# Codec.net
KiCad netlist of a schematic drawn in Altium Designer
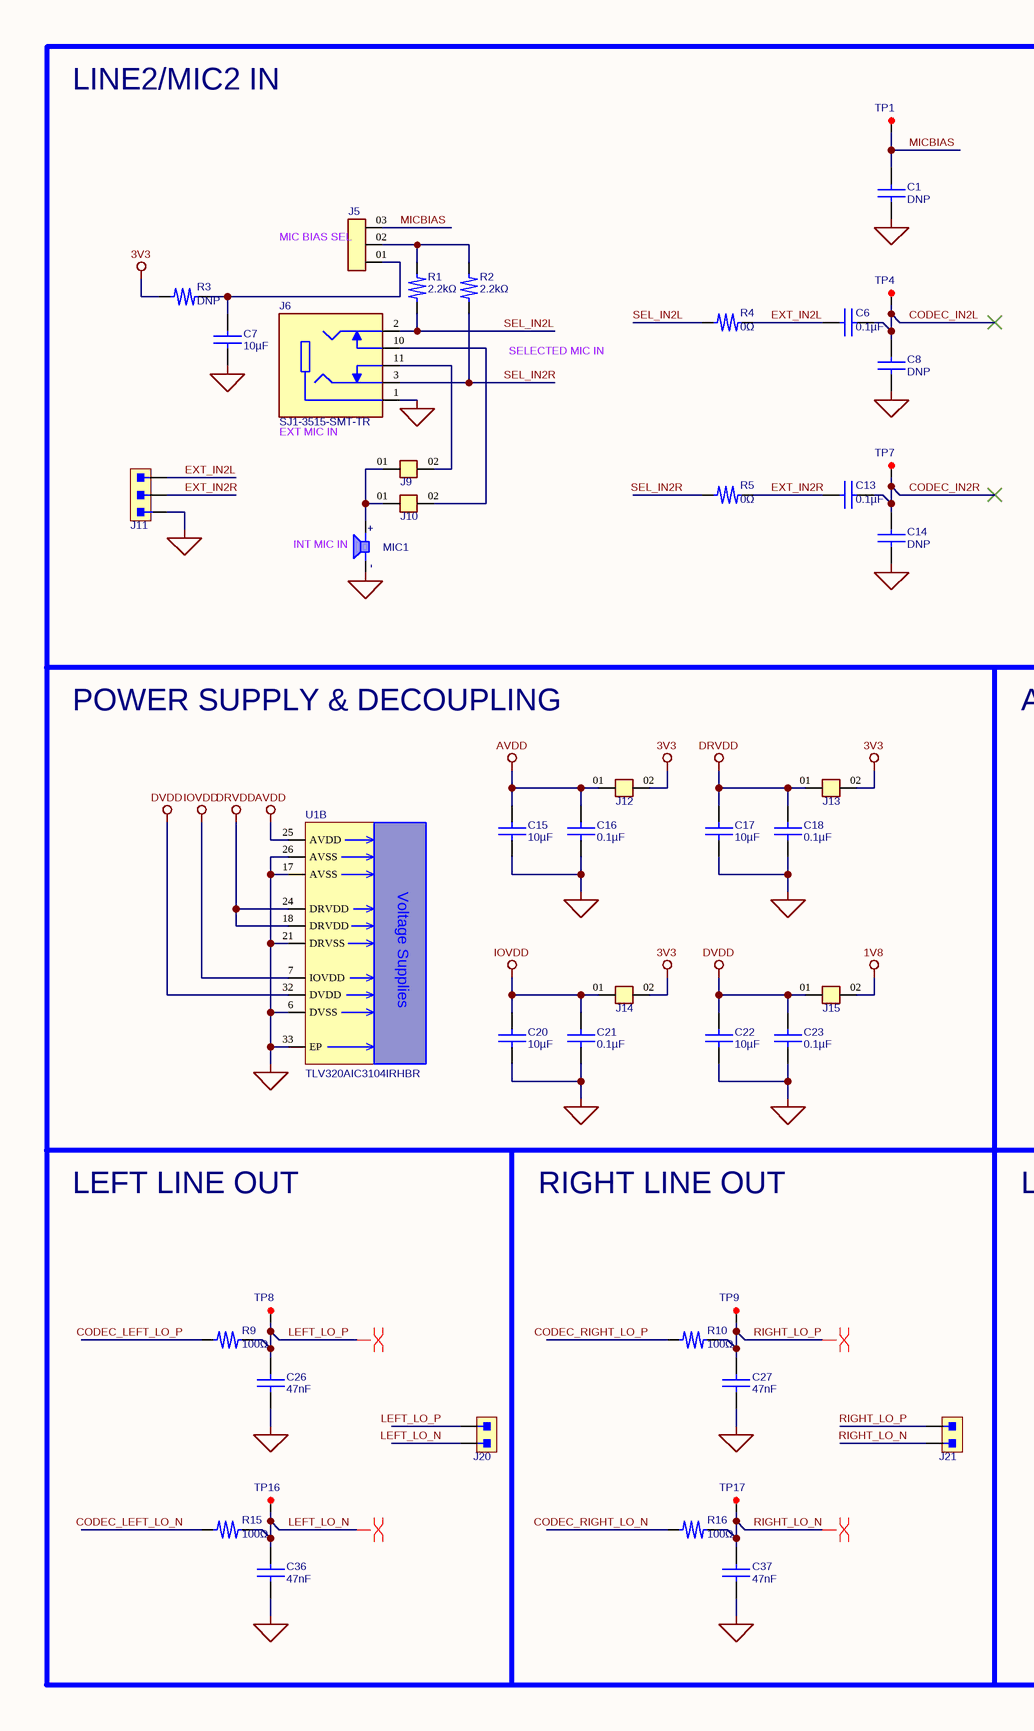
[diagram p0: Codec.SchDoc, left]
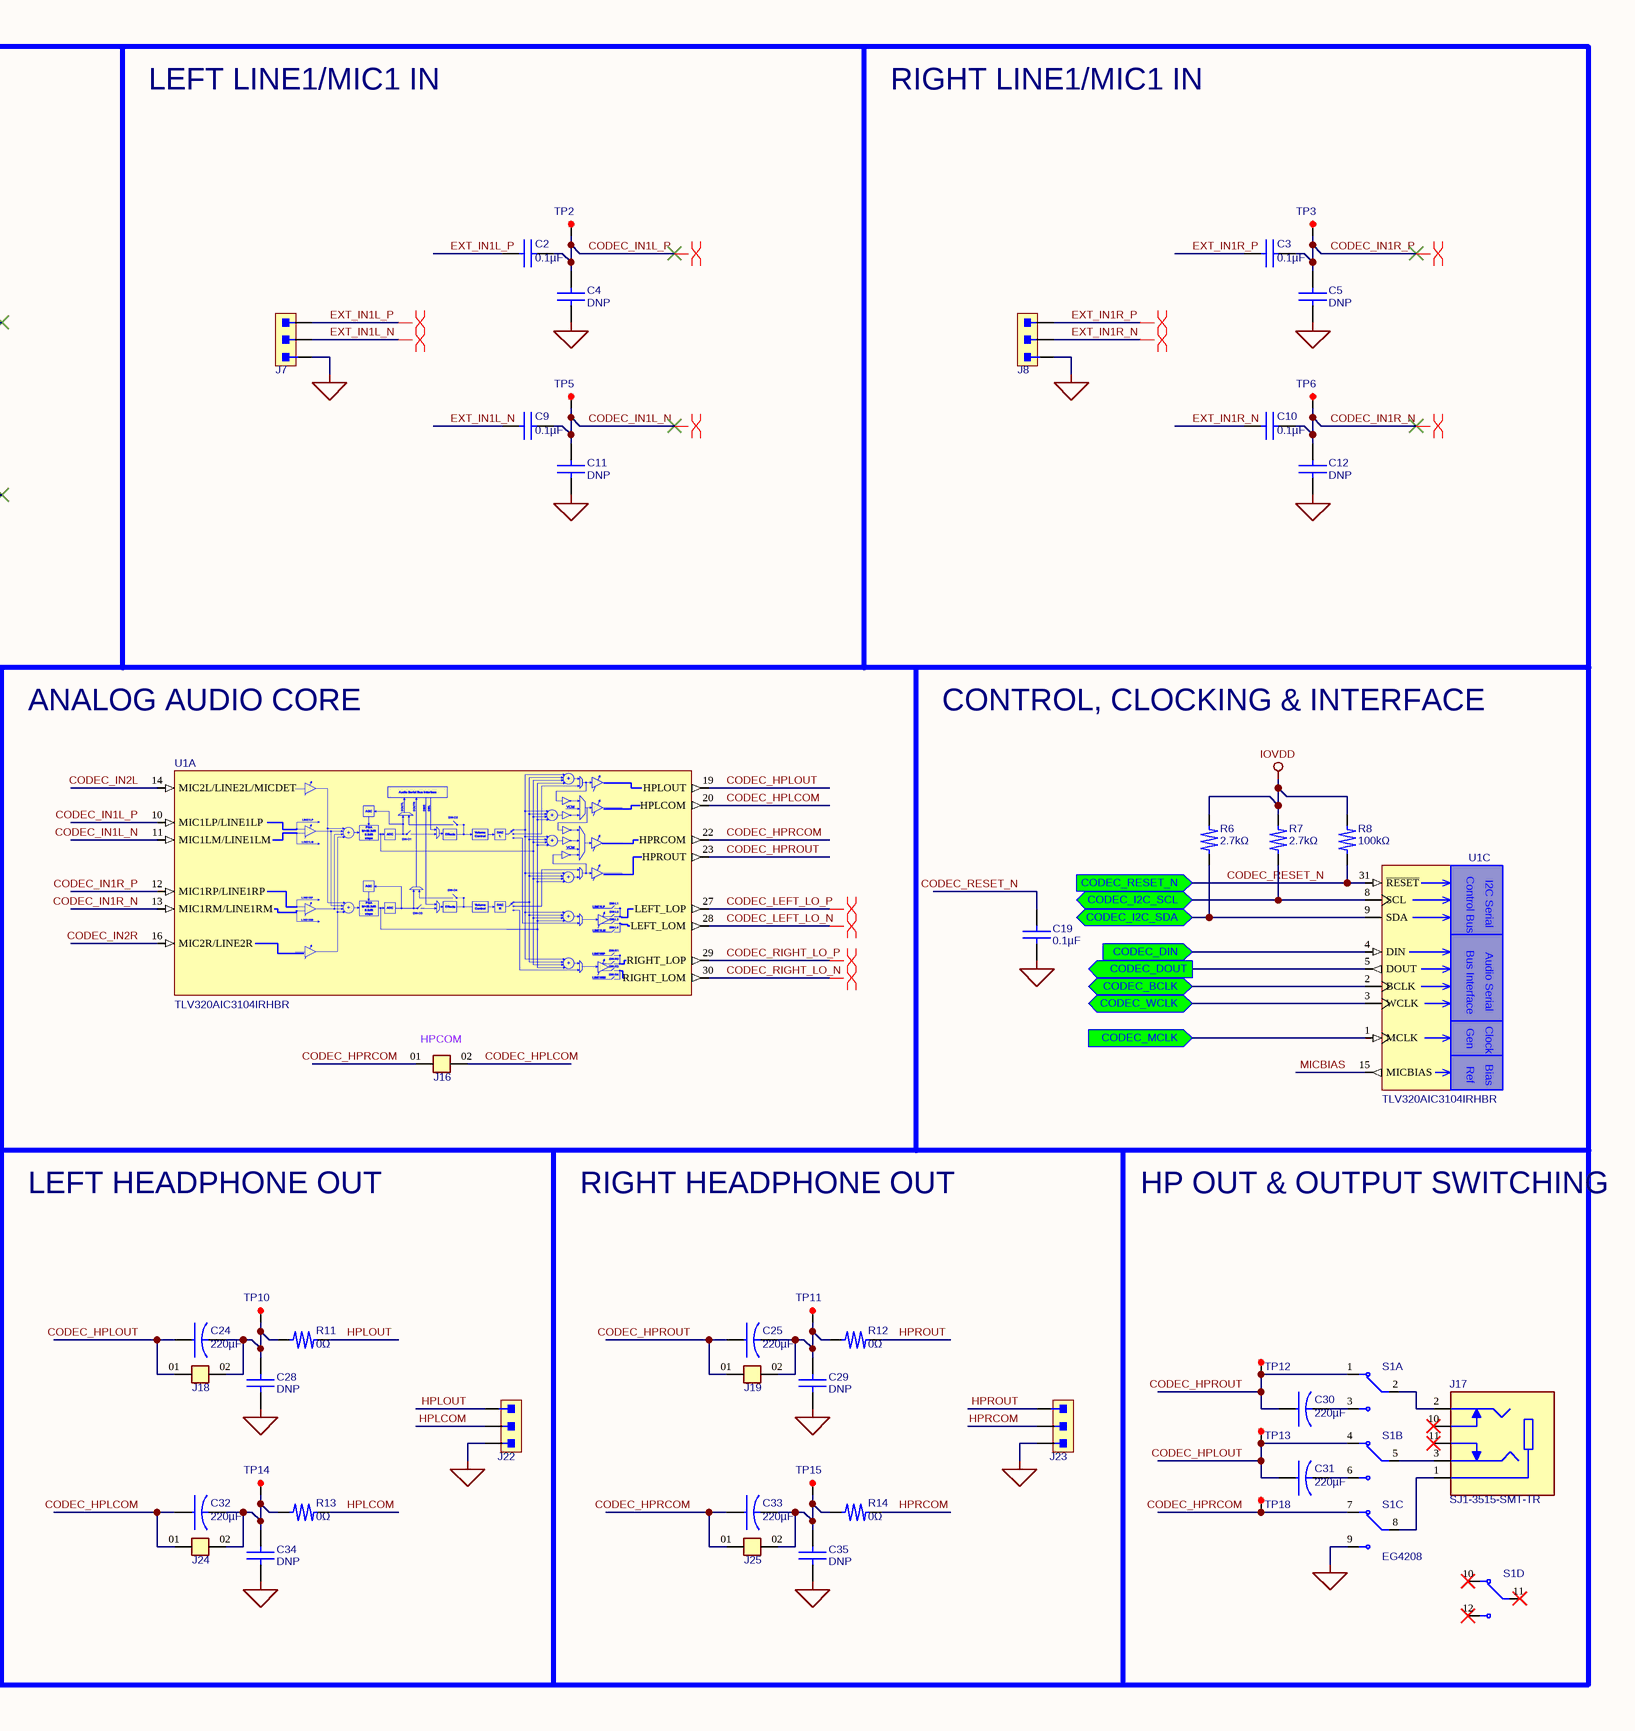
[diagram p1: Codec.SchDoc, right]

(export (version "E")
  (design (tool "Eeschema 10.0.6"))
  (components
    (comp (ref "C1")
      (value "DNP")
      (footprint "CAPC3216")
      (description "Do Not Populate 1206 (3216 Metric)")
      (fields (field (name "Comment") "DNP_1206"))
      (libsource (lib "Capacitors") (part "DNP_1206"))
    )
    (comp (ref "C2")
      (value "0.1µF")
      (footprint "CAPC3216")
      (description "Multilayer Ceramic Capacitor, C Series, 0.1 - F, - 10%, X7R, 100 V, 1206 [3216 Metric]")
      (fields
        (field (name "MANUFACTURER") "TDK")
        (field (name "MANUFACTURER PART NUMBER") "C3216X7R2A104K160AA")
      )
      (libsource (lib "Capacitors") (part "C3216X7R2A104K160AA"))
    )
    (comp (ref "C3")
      (value "0.1µF")
      (footprint "CAPC3216")
      (description "Multilayer Ceramic Capacitor, C Series, 0.1 - F, - 10%, X7R, 100 V, 1206 [3216 Metric]")
      (fields
        (field (name "MANUFACTURER") "TDK")
        (field (name "MANUFACTURER PART NUMBER") "C3216X7R2A104K160AA")
      )
      (libsource (lib "Capacitors") (part "C3216X7R2A104K160AA"))
    )
    (comp (ref "C4")
      (value "DNP")
      (footprint "CAPC3216")
      (description "Do Not Populate 1206 (3216 Metric)")
      (fields (field (name "Comment") "DNP_1206"))
      (libsource (lib "Capacitors") (part "DNP_1206"))
    )
    (comp (ref "C5")
      (value "DNP")
      (footprint "CAPC3216")
      (description "Do Not Populate 1206 (3216 Metric)")
      (fields (field (name "Comment") "DNP_1206"))
      (libsource (lib "Capacitors") (part "DNP_1206"))
    )
    (comp (ref "C6")
      (value "0.1µF")
      (footprint "CAPC3216")
      (description "Multilayer Ceramic Capacitor, C Series, 0.1 - F, - 10%, X7R, 100 V, 1206 [3216 Metric]")
      (fields
        (field (name "MANUFACTURER") "TDK")
        (field (name "MANUFACTURER PART NUMBER") "C3216X7R2A104K160AA")
      )
      (libsource (lib "Capacitors") (part "C3216X7R2A104K160AA"))
    )
    (comp (ref "C7")
      (value "10µF")
      (footprint "CAPC3225")
      (fields
        (field (name "MANUFACTURER") "TDK")
        (field (name "MANUFACTURER PART NUMBER") "C3225X7R1H106K250AC")
      )
      (libsource (lib "Capacitors") (part "C3225X7R1H106K250AC"))
    )
    (comp (ref "C8")
      (value "DNP")
      (footprint "CAPC3216")
      (description "Do Not Populate 1206 (3216 Metric)")
      (fields (field (name "Comment") "DNP_1206"))
      (libsource (lib "Capacitors") (part "DNP_1206"))
    )
    (comp (ref "C9")
      (value "0.1µF")
      (footprint "CAPC3216")
      (description "Multilayer Ceramic Capacitor, C Series, 0.1 - F, - 10%, X7R, 100 V, 1206 [3216 Metric]")
      (fields
        (field (name "MANUFACTURER") "TDK")
        (field (name "MANUFACTURER PART NUMBER") "C3216X7R2A104K160AA")
      )
      (libsource (lib "Capacitors") (part "C3216X7R2A104K160AA"))
    )
    (comp (ref "C10")
      (value "0.1µF")
      (footprint "CAPC3216")
      (description "Multilayer Ceramic Capacitor, C Series, 0.1 - F, - 10%, X7R, 100 V, 1206 [3216 Metric]")
      (fields
        (field (name "MANUFACTURER") "TDK")
        (field (name "MANUFACTURER PART NUMBER") "C3216X7R2A104K160AA")
      )
      (libsource (lib "Capacitors") (part "C3216X7R2A104K160AA"))
    )
    (comp (ref "C11")
      (value "DNP")
      (footprint "CAPC3216")
      (description "Do Not Populate 1206 (3216 Metric)")
      (fields (field (name "Comment") "DNP_1206"))
      (libsource (lib "Capacitors") (part "DNP_1206"))
    )
    (comp (ref "C12")
      (value "DNP")
      (footprint "CAPC3216")
      (description "Do Not Populate 1206 (3216 Metric)")
      (fields (field (name "Comment") "DNP_1206"))
      (libsource (lib "Capacitors") (part "DNP_1206"))
    )
    (comp (ref "C13")
      (value "0.1µF")
      (footprint "CAPC3216")
      (description "Multilayer Ceramic Capacitor, C Series, 0.1 - F, - 10%, X7R, 100 V, 1206 [3216 Metric]")
      (fields
        (field (name "MANUFACTURER") "TDK")
        (field (name "MANUFACTURER PART NUMBER") "C3216X7R2A104K160AA")
      )
      (libsource (lib "Capacitors") (part "C3216X7R2A104K160AA"))
    )
    (comp (ref "C14")
      (value "DNP")
      (footprint "CAPC3216")
      (description "Do Not Populate 1206 (3216 Metric)")
      (fields (field (name "Comment") "DNP_1206"))
      (libsource (lib "Capacitors") (part "DNP_1206"))
    )
    (comp (ref "C15")
      (value "10µF")
      (footprint "CAPC3225")
      (fields
        (field (name "MANUFACTURER") "TDK")
        (field (name "MANUFACTURER PART NUMBER") "C3225X7R1H106K250AC")
      )
      (libsource (lib "Capacitors") (part "C3225X7R1H106K250AC"))
    )
    (comp (ref "C16")
      (value "0.1µF")
      (footprint "CAPC1608")
      (description "0603 (1608METRIC) Ceramic Capacitor SMD Indust X7R HT175C 50V 0.1MUF ±10% X7R")
      (fields
        (field (name "MANUFACTURER") "KEMET")
        (field (name "MANUFACTURER PART NUMBER") "C0603G104K5RACT500")
      )
      (libsource (lib "Capacitors") (part "C0603G104K5RACT500"))
    )
    (comp (ref "C17")
      (value "10µF")
      (footprint "CAPC3225")
      (fields
        (field (name "MANUFACTURER") "TDK")
        (field (name "MANUFACTURER PART NUMBER") "C3225X7R1H106K250AC")
      )
      (libsource (lib "Capacitors") (part "C3225X7R1H106K250AC"))
    )
    (comp (ref "C18")
      (value "0.1µF")
      (footprint "CAPC1608")
      (description "0603 (1608METRIC) Ceramic Capacitor SMD Indust X7R HT175C 50V 0.1MUF ±10% X7R")
      (fields
        (field (name "MANUFACTURER") "KEMET")
        (field (name "MANUFACTURER PART NUMBER") "C0603G104K5RACT500")
      )
      (libsource (lib "Capacitors") (part "C0603G104K5RACT500"))
    )
    (comp (ref "C19")
      (value "0.1µF")
      (footprint "CAPC1608")
      (description "0603 (1608METRIC) Ceramic Capacitor SMD Indust X7R HT175C 50V 0.1MUF ±10% X7R")
      (fields
        (field (name "MANUFACTURER") "KEMET")
        (field (name "MANUFACTURER PART NUMBER") "C0603G104K5RACT500")
      )
      (libsource (lib "Capacitors") (part "C0603G104K5RACT500"))
    )
    (comp (ref "C20")
      (value "10µF")
      (footprint "CAPC3225")
      (fields
        (field (name "MANUFACTURER") "TDK")
        (field (name "MANUFACTURER PART NUMBER") "C3225X7R1H106K250AC")
      )
      (libsource (lib "Capacitors") (part "C3225X7R1H106K250AC"))
    )
    (comp (ref "C21")
      (value "0.1µF")
      (footprint "CAPC1608")
      (description "0603 (1608METRIC) Ceramic Capacitor SMD Indust X7R HT175C 50V 0.1MUF ±10% X7R")
      (fields
        (field (name "MANUFACTURER") "KEMET")
        (field (name "MANUFACTURER PART NUMBER") "C0603G104K5RACT500")
      )
      (libsource (lib "Capacitors") (part "C0603G104K5RACT500"))
    )
    (comp (ref "C22")
      (value "10µF")
      (footprint "CAPC3225")
      (fields
        (field (name "MANUFACTURER") "TDK")
        (field (name "MANUFACTURER PART NUMBER") "C3225X7R1H106K250AC")
      )
      (libsource (lib "Capacitors") (part "C3225X7R1H106K250AC"))
    )
    (comp (ref "C23")
      (value "0.1µF")
      (footprint "CAPC1608")
      (description "0603 (1608METRIC) Ceramic Capacitor SMD Indust X7R HT175C 50V 0.1MUF ±10% X7R")
      (fields
        (field (name "MANUFACTURER") "KEMET")
        (field (name "MANUFACTURER PART NUMBER") "C0603G104K5RACT500")
      )
      (libsource (lib "Capacitors") (part "C0603G104K5RACT500"))
    )
    (comp (ref "C24")
      (value "220µF")
      (footprint "CAPPRD500W60D800H1150")
      (description "Radial Can ALUMINUM ELECTROLYTIC CAPACITOR FR 25V 220muF ±20% 0.315Dia 8.00mm")
      (fields
        (field (name "MANUFACTURER") "Panasonic")
        (field (name "MANUFACTURER PART NUMBER") "EEU-FR1E221B")
      )
      (libsource (lib "Capacitors") (part "EEU-FR1E221B"))
    )
    (comp (ref "C25")
      (value "220µF")
      (footprint "CAPPRD500W60D800H1150")
      (description "Radial Can ALUMINUM ELECTROLYTIC CAPACITOR FR 25V 220muF ±20% 0.315Dia 8.00mm")
      (fields
        (field (name "MANUFACTURER") "Panasonic")
        (field (name "MANUFACTURER PART NUMBER") "EEU-FR1E221B")
      )
      (libsource (lib "Capacitors") (part "EEU-FR1E221B"))
    )
    (comp (ref "C26")
      (value "47nF")
      (footprint "CAPC1608")
      (description "50V 47nF X7R 卤10% 0603 Multilayer Ceramic Capacitors MLCC - SMD/SMT ROHS")
      (fields
        (field (name "MANUFACTURER") "TDK")
        (field (name "MANUFACTURER PART NUMBER") "C1608X7R1H473K080AE")
      )
      (libsource (lib "Capacitors") (part "C1608X7R1H473K080AE"))
    )
    (comp (ref "C27")
      (value "47nF")
      (footprint "CAPC1608")
      (description "50V 47nF X7R 卤10% 0603 Multilayer Ceramic Capacitors MLCC - SMD/SMT ROHS")
      (fields
        (field (name "MANUFACTURER") "TDK")
        (field (name "MANUFACTURER PART NUMBER") "C1608X7R1H473K080AE")
      )
      (libsource (lib "Capacitors") (part "C1608X7R1H473K080AE"))
    )
    (comp (ref "C28")
      (value "DNP")
      (footprint "CAPC3216")
      (description "Do Not Populate 1206 (3216 Metric)")
      (fields (field (name "Comment") "DNP_1206"))
      (libsource (lib "Capacitors") (part "DNP_1206"))
    )
    (comp (ref "C29")
      (value "DNP")
      (footprint "CAPC3216")
      (description "Do Not Populate 1206 (3216 Metric)")
      (fields (field (name "Comment") "DNP_1206"))
      (libsource (lib "Capacitors") (part "DNP_1206"))
    )
    (comp (ref "C30")
      (value "220µF")
      (footprint "CAPPRD500W60D800H1150")
      (description "Radial Can ALUMINUM ELECTROLYTIC CAPACITOR FR 25V 220muF ±20% 0.315Dia 8.00mm")
      (fields
        (field (name "MANUFACTURER") "Panasonic")
        (field (name "MANUFACTURER PART NUMBER") "EEU-FR1E221B")
      )
      (libsource (lib "Capacitors") (part "EEU-FR1E221B"))
    )
    (comp (ref "C31")
      (value "220µF")
      (footprint "CAPPRD500W60D800H1150")
      (description "Radial Can ALUMINUM ELECTROLYTIC CAPACITOR FR 25V 220muF ±20% 0.315Dia 8.00mm")
      (fields
        (field (name "MANUFACTURER") "Panasonic")
        (field (name "MANUFACTURER PART NUMBER") "EEU-FR1E221B")
      )
      (libsource (lib "Capacitors") (part "EEU-FR1E221B"))
    )
    (comp (ref "C32")
      (value "220µF")
      (footprint "CAPPRD500W60D800H1150")
      (description "Radial Can ALUMINUM ELECTROLYTIC CAPACITOR FR 25V 220muF ±20% 0.315Dia 8.00mm")
      (fields
        (field (name "MANUFACTURER") "Panasonic")
        (field (name "MANUFACTURER PART NUMBER") "EEU-FR1E221B")
      )
      (libsource (lib "Capacitors") (part "EEU-FR1E221B"))
    )
    (comp (ref "C33")
      (value "220µF")
      (footprint "CAPPRD500W60D800H1150")
      (description "Radial Can ALUMINUM ELECTROLYTIC CAPACITOR FR 25V 220muF ±20% 0.315Dia 8.00mm")
      (fields
        (field (name "MANUFACTURER") "Panasonic")
        (field (name "MANUFACTURER PART NUMBER") "EEU-FR1E221B")
      )
      (libsource (lib "Capacitors") (part "EEU-FR1E221B"))
    )
    (comp (ref "C34")
      (value "DNP")
      (footprint "CAPC3216")
      (description "Do Not Populate 1206 (3216 Metric)")
      (fields (field (name "Comment") "DNP_1206"))
      (libsource (lib "Capacitors") (part "DNP_1206"))
    )
    (comp (ref "C35")
      (value "DNP")
      (footprint "CAPC3216")
      (description "Do Not Populate 1206 (3216 Metric)")
      (fields (field (name "Comment") "DNP_1206"))
      (libsource (lib "Capacitors") (part "DNP_1206"))
    )
    (comp (ref "C36")
      (value "47nF")
      (footprint "CAPC1608")
      (description "50V 47nF X7R 卤10% 0603 Multilayer Ceramic Capacitors MLCC - SMD/SMT ROHS")
      (fields
        (field (name "MANUFACTURER") "TDK")
        (field (name "MANUFACTURER PART NUMBER") "C1608X7R1H473K080AE")
      )
      (libsource (lib "Capacitors") (part "C1608X7R1H473K080AE"))
    )
    (comp (ref "C37")
      (value "47nF")
      (footprint "CAPC1608")
      (description "50V 47nF X7R 卤10% 0603 Multilayer Ceramic Capacitors MLCC - SMD/SMT ROHS")
      (fields
        (field (name "MANUFACTURER") "TDK")
        (field (name "MANUFACTURER PART NUMBER") "C1608X7R1H473K080AE")
      )
      (libsource (lib "Capacitors") (part "C1608X7R1H473K080AE"))
    )
    (comp (ref "J5")
      (value "M20-9990346")
      (footprint "HARWIN_M20-9990346")
      (description "M20 ROHS3Compliant COMMERCIAL UL Connector Header, Cuttable 50Cycles 30mOhm -40C~105C 3A")
      (fields (field (name "MANUFACTURER") "Harwin Inc."))
      (libsource (lib "Connectors") (part "M20-9990346"))
    )
    (comp (ref "J6")
      (value "SJ1-3515-SMT-TR")
      (footprint "SAMESKY_SJ1-3515-SMT")
      (description "3.5 mm, Stereo, Right Angle, Surface Mount (SMT), Audio Jack Connector")
      (fields (field (name "MANUFACTURER") "Same Sky (Formerly CUI Devices)"))
      (libsource (lib "") (part "SJ1-3515-SMT-TR_1"))
    )
    (comp (ref "J7")
      (value "397730003")
      (footprint "MOLEX_0397730003")
      (description "2.54mm Pitch Beau Eurostyle Fixed Mount PCB Terminal Block, Green, 3 Circuits")
      (fields (field (name "MANUFACTURER") "Molex") (field (name "MANUFACTURER PART NUMBER") "0397730003"))
      (libsource (lib "Connectors") (part "397730003"))
    )
    (comp (ref "J8")
      (value "397730003")
      (footprint "MOLEX_0397730003")
      (description "2.54mm Pitch Beau Eurostyle Fixed Mount PCB Terminal Block, Green, 3 Circuits")
      (fields (field (name "MANUFACTURER") "Molex") (field (name "MANUFACTURER PART NUMBER") "0397730003"))
      (libsource (lib "Connectors") (part "397730003"))
    )
    (comp (ref "J9")
      (value "HTSW-102-07-G-S")
      (footprint "SAMTEC_HTSW-102-XX-X-S")
      (description "Pin Header, Vertical, Board-to-Board, 2.54 mm, 1 Rows, 2 Contacts, Through Hole, HTSW")
      (fields (field (name "MANUFACTURER") "Samtec Inc."))
      (libsource (lib "Connectors") (part "HTSW-102-07-G-S"))
    )
    (comp (ref "J10")
      (value "HTSW-102-07-G-S")
      (footprint "SAMTEC_HTSW-102-XX-X-S")
      (description "Pin Header, Vertical, Board-to-Board, 2.54 mm, 1 Rows, 2 Contacts, Through Hole, HTSW")
      (fields (field (name "MANUFACTURER") "Samtec Inc."))
      (libsource (lib "Connectors") (part "HTSW-102-07-G-S"))
    )
    (comp (ref "J11")
      (value "397730003")
      (footprint "MOLEX_0397730003")
      (description "2.54mm Pitch Beau Eurostyle Fixed Mount PCB Terminal Block, Green, 3 Circuits")
      (fields (field (name "MANUFACTURER") "Molex") (field (name "MANUFACTURER PART NUMBER") "0397730003"))
      (libsource (lib "Connectors") (part "397730003"))
    )
    (comp (ref "J12")
      (value "HTSW-102-07-G-S")
      (footprint "SAMTEC_HTSW-102-XX-X-S")
      (description "Pin Header, Vertical, Board-to-Board, 2.54 mm, 1 Rows, 2 Contacts, Through Hole, HTSW")
      (fields (field (name "MANUFACTURER") "Samtec Inc."))
      (libsource (lib "Connectors") (part "HTSW-102-07-G-S"))
    )
    (comp (ref "J13")
      (value "HTSW-102-07-G-S")
      (footprint "SAMTEC_HTSW-102-XX-X-S")
      (description "Pin Header, Vertical, Board-to-Board, 2.54 mm, 1 Rows, 2 Contacts, Through Hole, HTSW")
      (fields (field (name "MANUFACTURER") "Samtec Inc."))
      (libsource (lib "Connectors") (part "HTSW-102-07-G-S"))
    )
    (comp (ref "J14")
      (value "HTSW-102-07-G-S")
      (footprint "SAMTEC_HTSW-102-XX-X-S")
      (description "Pin Header, Vertical, Board-to-Board, 2.54 mm, 1 Rows, 2 Contacts, Through Hole, HTSW")
      (fields (field (name "MANUFACTURER") "Samtec Inc."))
      (libsource (lib "Connectors") (part "HTSW-102-07-G-S"))
    )
    (comp (ref "J15")
      (value "HTSW-102-07-G-S")
      (footprint "SAMTEC_HTSW-102-XX-X-S")
      (description "Pin Header, Vertical, Board-to-Board, 2.54 mm, 1 Rows, 2 Contacts, Through Hole, HTSW")
      (fields (field (name "MANUFACTURER") "Samtec Inc."))
      (libsource (lib "Connectors") (part "HTSW-102-07-G-S"))
    )
    (comp (ref "J16")
      (value "HTSW-102-07-G-S")
      (footprint "SAMTEC_HTSW-102-XX-X-S")
      (description "Pin Header, Vertical, Board-to-Board, 2.54 mm, 1 Rows, 2 Contacts, Through Hole, HTSW")
      (fields (field (name "MANUFACTURER") "Samtec Inc."))
      (libsource (lib "Connectors") (part "HTSW-102-07-G-S"))
    )
    (comp (ref "J17")
      (value "SJ1-3515-SMT-TR")
      (footprint "SAMESKY_SJ1-3515-SMT")
      (description "3.5 mm, Stereo, Right Angle, Surface Mount (SMT), Audio Jack Connector")
      (fields (field (name "MANUFACTURER") "Same Sky (Formerly CUI Devices)"))
      (libsource (lib "Connectors") (part "SJ1-3515-SMT-TR"))
    )
    (comp (ref "J18")
      (value "HTSW-102-07-G-S")
      (footprint "SAMTEC_HTSW-102-XX-X-S")
      (description "Pin Header, Vertical, Board-to-Board, 2.54 mm, 1 Rows, 2 Contacts, Through Hole, HTSW")
      (fields (field (name "MANUFACTURER") "Samtec Inc."))
      (libsource (lib "Connectors") (part "HTSW-102-07-G-S"))
    )
    (comp (ref "J19")
      (value "HTSW-102-07-G-S")
      (footprint "SAMTEC_HTSW-102-XX-X-S")
      (description "Pin Header, Vertical, Board-to-Board, 2.54 mm, 1 Rows, 2 Contacts, Through Hole, HTSW")
      (fields (field (name "MANUFACTURER") "Samtec Inc."))
      (libsource (lib "Connectors") (part "HTSW-102-07-G-S"))
    )
    (comp (ref "J20")
      (value "0397730002")
      (footprint "MOLEX_0397730002")
      (description "2.54mm Pitch Beau Eurostyle Fixed Mount PCB Terminal Block, Green, 2 Circuits")
      (fields (field (name "MANUFACTURER") "Molex"))
      (libsource (lib "Connectors") (part "0397730002"))
    )
    (comp (ref "J21")
      (value "0397730002")
      (footprint "MOLEX_0397730002")
      (description "2.54mm Pitch Beau Eurostyle Fixed Mount PCB Terminal Block, Green, 2 Circuits")
      (fields (field (name "MANUFACTURER") "Molex"))
      (libsource (lib "Connectors") (part "0397730002"))
    )
    (comp (ref "J22")
      (value "397730003")
      (footprint "MOLEX_0397730003")
      (description "2.54mm Pitch Beau Eurostyle Fixed Mount PCB Terminal Block, Green, 3 Circuits")
      (fields (field (name "MANUFACTURER") "Molex") (field (name "MANUFACTURER PART NUMBER") "0397730003"))
      (libsource (lib "") (part "397730003_1"))
    )
    (comp (ref "J23")
      (value "397730003")
      (footprint "MOLEX_0397730003")
      (description "2.54mm Pitch Beau Eurostyle Fixed Mount PCB Terminal Block, Green, 3 Circuits")
      (fields (field (name "MANUFACTURER") "Molex") (field (name "MANUFACTURER PART NUMBER") "0397730003"))
      (libsource (lib "") (part "397730003_1"))
    )
    (comp (ref "J24")
      (value "HTSW-102-07-G-S")
      (footprint "SAMTEC_HTSW-102-XX-X-S")
      (description "Pin Header, Vertical, Board-to-Board, 2.54 mm, 1 Rows, 2 Contacts, Through Hole, HTSW")
      (fields (field (name "MANUFACTURER") "Samtec Inc."))
      (libsource (lib "Connectors") (part "HTSW-102-07-G-S"))
    )
    (comp (ref "J25")
      (value "HTSW-102-07-G-S")
      (footprint "SAMTEC_HTSW-102-XX-X-S")
      (description "Pin Header, Vertical, Board-to-Board, 2.54 mm, 1 Rows, 2 Contacts, Through Hole, HTSW")
      (fields (field (name "MANUFACTURER") "Samtec Inc."))
      (libsource (lib "Connectors") (part "HTSW-102-07-G-S"))
    )
    (comp (ref "MIC1")
      (value "AOM-4544P-2-R")
      (footprint "MIC_PUIAUDIO_AOM-4544P-2-R")
      (fields (field (name "MANUFACTURER") "PUI Audio, Inc."))
      (libsource (lib "Microphones") (part "AOM-4544P-2-R"))
    )
    (comp (ref "R1")
      (value "2.2kΩ")
      (footprint "RESC3216")
      (description "Res Thick Film 1206 2.2K Ohm 5% 1/4W ±200ppm/°C Molded SMD Punched Carrier T/R")
      (fields
        (field (name "MANUFACTURER") "Panasonic Industry")
        (field (name "MANUFACTURER PART NUMBER") "ERJ-8GEYJ222V")
      )
      (libsource (lib "Resistors") (part "ERJ-8GEYJ222V"))
    )
    (comp (ref "R2")
      (value "2.2kΩ")
      (footprint "RESC3216")
      (description "Res Thick Film 1206 2.2K Ohm 5% 1/4W ±200ppm/°C Molded SMD Punched Carrier T/R")
      (fields
        (field (name "MANUFACTURER") "Panasonic Industry")
        (field (name "MANUFACTURER PART NUMBER") "ERJ-8GEYJ222V")
      )
      (libsource (lib "Resistors") (part "ERJ-8GEYJ222V"))
    )
    (comp (ref "R3")
      (value "DNP")
      (footprint "RESC3216")
      (description "Do Not Populate 1206 (3216 Metric)")
      (fields (field (name "Comment") "DNP_1206"))
      (libsource (lib "Resistors") (part "DNP_1206"))
    )
    (comp (ref "R4")
      (value "0Ω")
      (footprint "RESC3216")
      (description "ERJ Series 1206 0 Ohm 0.25 W Jumper Surface Mount Thick Film Chip Resistor")
      (fields
        (field (name "MANUFACTURER") "Panasonic Industry")
        (field (name "MANUFACTURER PART NUMBER") "ERJ-8GEY0R00V")
      )
      (libsource (lib "Resistors") (part "ERJ-8GEY0R00V"))
    )
    (comp (ref "R5")
      (value "0Ω")
      (footprint "RESC3216")
      (description "ERJ Series 1206 0 Ohm 0.25 W Jumper Surface Mount Thick Film Chip Resistor")
      (fields
        (field (name "MANUFACTURER") "Panasonic Industry")
        (field (name "MANUFACTURER PART NUMBER") "ERJ-8GEY0R00V")
      )
      (libsource (lib "Resistors") (part "ERJ-8GEY0R00V"))
    )
    (comp (ref "R6")
      (value "2.7kΩ")
      (footprint "RESC1608")
      (description "Res Thick Film 0603 2.7K Ohm 5% 0.1W(1/10W) ±200ppm/C Pad SMD T/R Automotive AEC-Q200")
      (fields
        (field (name "MANUFACTURER") "Panasonic Industry")
        (field (name "MANUFACTURER PART NUMBER") "ERJ-3GEYJ272V")
      )
      (libsource (lib "Resistors") (part "ERJ-3GEYJ272V"))
    )
    (comp (ref "R7")
      (value "2.7kΩ")
      (footprint "RESC1608")
      (description "Res Thick Film 0603 2.7K Ohm 5% 0.1W(1/10W) ±200ppm/C Pad SMD T/R Automotive AEC-Q200")
      (fields
        (field (name "MANUFACTURER") "Panasonic Industry")
        (field (name "MANUFACTURER PART NUMBER") "ERJ-3GEYJ272V")
      )
      (libsource (lib "Resistors") (part "ERJ-3GEYJ272V"))
    )
    (comp (ref "R8")
      (value "100kΩ")
      (footprint "RESC1608")
      (description "Res General Purpose Thick Film 0603 100k Ohm 1% 1/10W ±100ppm/°C Molded Paper T/R")
      (fields
        (field (name "MANUFACTURER") "Yageo Group")
        (field (name "MANUFACTURER PART NUMBER") "RC0603FR-07100KL")
      )
      (libsource (lib "Resistors") (part "RC0603FR-07100KL"))
    )
    (comp (ref "R9")
      (value "100Ω")
      (footprint "RESC1608")
      (description "Res Thick Film 0603 100 Ohm 1% 1/10W ±100ppm/°C Molded SMD Paper T/R")
      (fields
        (field (name "MANUFACTURER") "Yageo Group")
        (field (name "MANUFACTURER PART NUMBER") "RC0603FR-07100RL")
      )
      (libsource (lib "Resistors") (part "RC0603FR-07100RL"))
    )
    (comp (ref "R10")
      (value "100Ω")
      (footprint "RESC1608")
      (description "Res Thick Film 0603 100 Ohm 1% 1/10W ±100ppm/°C Molded SMD Paper T/R")
      (fields
        (field (name "MANUFACTURER") "Yageo Group")
        (field (name "MANUFACTURER PART NUMBER") "RC0603FR-07100RL")
      )
      (libsource (lib "Resistors") (part "RC0603FR-07100RL"))
    )
    (comp (ref "R11")
      (value "0Ω")
      (footprint "RESC3216")
      (description "ERJ Series 1206 0 Ohm 0.25 W Jumper Surface Mount Thick Film Chip Resistor")
      (fields
        (field (name "MANUFACTURER") "Panasonic Industry")
        (field (name "MANUFACTURER PART NUMBER") "ERJ-8GEY0R00V")
      )
      (libsource (lib "Resistors") (part "ERJ-8GEY0R00V"))
    )
    (comp (ref "R12")
      (value "0Ω")
      (footprint "RESC3216")
      (description "ERJ Series 1206 0 Ohm 0.25 W Jumper Surface Mount Thick Film Chip Resistor")
      (fields
        (field (name "MANUFACTURER") "Panasonic Industry")
        (field (name "MANUFACTURER PART NUMBER") "ERJ-8GEY0R00V")
      )
      (libsource (lib "Resistors") (part "ERJ-8GEY0R00V"))
    )
    (comp (ref "R13")
      (value "0Ω")
      (footprint "RESC3216")
      (description "ERJ Series 1206 0 Ohm 0.25 W Jumper Surface Mount Thick Film Chip Resistor")
      (fields
        (field (name "MANUFACTURER") "Panasonic Industry")
        (field (name "MANUFACTURER PART NUMBER") "ERJ-8GEY0R00V")
      )
      (libsource (lib "Resistors") (part "ERJ-8GEY0R00V"))
    )
    (comp (ref "R14")
      (value "0Ω")
      (footprint "RESC3216")
      (description "ERJ Series 1206 0 Ohm 0.25 W Jumper Surface Mount Thick Film Chip Resistor")
      (fields
        (field (name "MANUFACTURER") "Panasonic Industry")
        (field (name "MANUFACTURER PART NUMBER") "ERJ-8GEY0R00V")
      )
      (libsource (lib "Resistors") (part "ERJ-8GEY0R00V"))
    )
    (comp (ref "R15")
      (value "100Ω")
      (footprint "RESC1608")
      (description "Res Thick Film 0603 100 Ohm 1% 1/10W ±100ppm/°C Molded SMD Paper T/R")
      (fields
        (field (name "MANUFACTURER") "Yageo Group")
        (field (name "MANUFACTURER PART NUMBER") "RC0603FR-07100RL")
      )
      (libsource (lib "Resistors") (part "RC0603FR-07100RL"))
    )
    (comp (ref "R16")
      (value "100Ω")
      (footprint "RESC1608")
      (description "Res Thick Film 0603 100 Ohm 1% 1/10W ±100ppm/°C Molded SMD Paper T/R")
      (fields
        (field (name "MANUFACTURER") "Yageo Group")
        (field (name "MANUFACTURER PART NUMBER") "RC0603FR-07100RL")
      )
      (libsource (lib "Resistors") (part "RC0603FR-07100RL"))
    )
    (comp (ref "S1")
      (value "EG4208")
      (footprint "SW_EG4208")
      (description "Slide Switch, EG Series, 4PDT, ON-ON, 4mm Actuator, 200mA DC, 30VDC, R/A PC ¦ E-Switch EG4208")
      (fields (field (name "MANUFACTURER") "E-Switch"))
      (libsource (lib "") (part "EG4208_2"))
    )
    (comp (ref "TP1")
      (value "5000")
      (footprint "KEYSTONE_5000")
      (fields (field (name "MANUFACTURER") "Keystone Electronics"))
      (libsource (lib "Connectors") (part "5000"))
    )
    (comp (ref "TP2")
      (value "5000")
      (footprint "KEYSTONE_5000")
      (fields (field (name "MANUFACTURER") "Keystone Electronics"))
      (libsource (lib "Connectors") (part "5000"))
    )
    (comp (ref "TP3")
      (value "5000")
      (footprint "KEYSTONE_5000")
      (fields (field (name "MANUFACTURER") "Keystone Electronics"))
      (libsource (lib "Connectors") (part "5000"))
    )
    (comp (ref "TP4")
      (value "5000")
      (footprint "KEYSTONE_5000")
      (fields (field (name "MANUFACTURER") "Keystone Electronics"))
      (libsource (lib "Connectors") (part "5000"))
    )
    (comp (ref "TP5")
      (value "5000")
      (footprint "KEYSTONE_5000")
      (fields (field (name "MANUFACTURER") "Keystone Electronics"))
      (libsource (lib "Connectors") (part "5000"))
    )
    (comp (ref "TP6")
      (value "5000")
      (footprint "KEYSTONE_5000")
      (fields (field (name "MANUFACTURER") "Keystone Electronics"))
      (libsource (lib "Connectors") (part "5000"))
    )
    (comp (ref "TP7")
      (value "5000")
      (footprint "KEYSTONE_5000")
      (fields (field (name "MANUFACTURER") "Keystone Electronics"))
      (libsource (lib "Connectors") (part "5000"))
    )
    (comp (ref "TP8")
      (value "5000")
      (footprint "KEYSTONE_5000")
      (fields (field (name "MANUFACTURER") "Keystone Electronics"))
      (libsource (lib "Connectors") (part "5000"))
    )
    (comp (ref "TP9")
      (value "5000")
      (footprint "KEYSTONE_5000")
      (fields (field (name "MANUFACTURER") "Keystone Electronics"))
      (libsource (lib "Connectors") (part "5000"))
    )
    (comp (ref "TP10")
      (value "5000")
      (footprint "KEYSTONE_5000")
      (fields (field (name "MANUFACTURER") "Keystone Electronics"))
      (libsource (lib "Connectors") (part "5000"))
    )
    (comp (ref "TP11")
      (value "5000")
      (footprint "KEYSTONE_5000")
      (fields (field (name "MANUFACTURER") "Keystone Electronics"))
      (libsource (lib "Connectors") (part "5000"))
    )
    (comp (ref "TP12")
      (value "5000")
      (footprint "KEYSTONE_5000")
      (fields (field (name "MANUFACTURER") "Keystone Electronics"))
      (libsource (lib "Connectors") (part "5000"))
    )
    (comp (ref "TP13")
      (value "5000")
      (footprint "KEYSTONE_5000")
      (fields (field (name "MANUFACTURER") "Keystone Electronics"))
      (libsource (lib "Connectors") (part "5000"))
    )
    (comp (ref "TP14")
      (value "5000")
      (footprint "KEYSTONE_5000")
      (fields (field (name "MANUFACTURER") "Keystone Electronics"))
      (libsource (lib "Connectors") (part "5000"))
    )
    (comp (ref "TP15")
      (value "5000")
      (footprint "KEYSTONE_5000")
      (fields (field (name "MANUFACTURER") "Keystone Electronics"))
      (libsource (lib "Connectors") (part "5000"))
    )
    (comp (ref "TP16")
      (value "5000")
      (footprint "KEYSTONE_5000")
      (fields (field (name "MANUFACTURER") "Keystone Electronics"))
      (libsource (lib "Connectors") (part "5000"))
    )
    (comp (ref "TP17")
      (value "5000")
      (footprint "KEYSTONE_5000")
      (fields (field (name "MANUFACTURER") "Keystone Electronics"))
      (libsource (lib "Connectors") (part "5000"))
    )
    (comp (ref "TP18")
      (value "5000")
      (footprint "KEYSTONE_5000")
      (fields (field (name "MANUFACTURER") "Keystone Electronics"))
      (libsource (lib "Connectors") (part "5000"))
    )
    (comp (ref "U1")
      (value "TLV320AIC3104IRHBR")
      (footprint "QFN50P500X500X100_HS-33N")
      (description "Low-Power Stereo CODEC with 6 Inputs, 6 Outputs, HP Amp and Enhanced Digital Effects")
      (fields (field (name "MANUFACTURER") "Texas Instruments"))
      (libsource (lib "ICs") (part "TLV320AIC3104IRHBR"))
    )
  )
  (nets
    (net (code "1") (name "/CODEC_BCLK") (class "Default")
      (node (ref "U1") (pin "2") (pinfunction "BCLK_2") (pintype "bidirectional"))
    )
    (net (code "2") (name "/CODEC_DIN") (class "Default")
      (node (ref "U1") (pin "4") (pinfunction "DIN_4") (pintype "input"))
    )
    (net (code "3") (name "/CODEC_DOUT") (class "Default")
      (node (ref "U1") (pin "5") (pinfunction "DOUT_5") (pintype "output"))
    )
    (net (code "4") (name "/CODEC_HPLCOM") (class "Default")
      (node (ref "C32") (pin "P") (pinfunction "P_P") (pintype "passive"))
      (node (ref "J16") (pin "02") (pinfunction "02_02") (pintype "passive"))
      (node (ref "J24") (pin "01") (pinfunction "01_01") (pintype "passive"))
      (node (ref "U1") (pin "20") (pinfunction "HPLCOM_20") (pintype "output"))
    )
    (net (code "5") (name "/CODEC_HPLOUT") (class "Default")
      (node (ref "C24") (pin "P") (pinfunction "P_P") (pintype "passive"))
      (node (ref "C31") (pin "P") (pinfunction "P_P") (pintype "passive"))
      (node (ref "J18") (pin "01") (pinfunction "01_01") (pintype "passive"))
      (node (ref "S1") (pin "4") (pinfunction "4_4") (pintype "passive"))
      (node (ref "TP13") (pin "TP") (pinfunction "TP_TP") (pintype "passive"))
      (node (ref "U1") (pin "19") (pinfunction "HPLOUT_19") (pintype "output"))
    )
    (net (code "6") (name "/CODEC_HPRCOM") (class "Default")
      (node (ref "C33") (pin "P") (pinfunction "P_P") (pintype "passive"))
      (node (ref "J16") (pin "01") (pinfunction "01_01") (pintype "passive"))
      (node (ref "J25") (pin "01") (pinfunction "01_01") (pintype "passive"))
      (node (ref "S1") (pin "7") (pinfunction "7_7") (pintype "passive"))
      (node (ref "TP18") (pin "TP") (pinfunction "TP_TP") (pintype "passive"))
      (node (ref "U1") (pin "22") (pinfunction "HPRCOM_22") (pintype "output"))
    )
    (net (code "7") (name "/CODEC_HPROUT") (class "Default")
      (node (ref "C25") (pin "P") (pinfunction "P_P") (pintype "passive"))
      (node (ref "C30") (pin "P") (pinfunction "P_P") (pintype "passive"))
      (node (ref "J19") (pin "01") (pinfunction "01_01") (pintype "passive"))
      (node (ref "S1") (pin "1") (pinfunction "1_1") (pintype "passive"))
      (node (ref "TP12") (pin "TP") (pinfunction "TP_TP") (pintype "passive"))
      (node (ref "U1") (pin "23") (pinfunction "HPROUT_23") (pintype "output"))
    )
    (net (code "8") (name "/CODEC_I2C_SCL") (class "Default")
      (node (ref "R7") (pin "1") (pinfunction "1_1") (pintype "passive"))
      (node (ref "U1") (pin "8") (pinfunction "SCL_8") (pintype "bidirectional"))
    )
    (net (code "9") (name "/CODEC_I2C_SDA") (class "Default")
      (node (ref "R6") (pin "1") (pinfunction "1_1") (pintype "passive"))
      (node (ref "U1") (pin "9") (pinfunction "SDA_9") (pintype "bidirectional"))
    )
    (net (code "10") (name "/CODEC_IN1L_N") (class "Default")
      (node (ref "C11") (pin "2") (pinfunction "2_2") (pintype "passive"))
      (node (ref "C9") (pin "2") (pinfunction "2_2") (pintype "passive"))
      (node (ref "TP5") (pin "TP") (pinfunction "TP_TP") (pintype "passive"))
      (node (ref "U1") (pin "11") (pinfunction "MIC1LM/LINE1LM_11") (pintype "input"))
    )
    (net (code "11") (name "/CODEC_IN1L_P") (class "Default")
      (node (ref "C2") (pin "2") (pinfunction "2_2") (pintype "passive"))
      (node (ref "C4") (pin "2") (pinfunction "2_2") (pintype "passive"))
      (node (ref "TP2") (pin "TP") (pinfunction "TP_TP") (pintype "passive"))
      (node (ref "U1") (pin "10") (pinfunction "MIC1LP/LINE1LP_10") (pintype "input"))
    )
    (net (code "12") (name "/CODEC_IN1R_N") (class "Default")
      (node (ref "C10") (pin "2") (pinfunction "2_2") (pintype "passive"))
      (node (ref "C12") (pin "2") (pinfunction "2_2") (pintype "passive"))
      (node (ref "TP6") (pin "TP") (pinfunction "TP_TP") (pintype "passive"))
      (node (ref "U1") (pin "13") (pinfunction "MIC1RM/LINE1RM_13") (pintype "input"))
    )
    (net (code "13") (name "/CODEC_IN1R_P") (class "Default")
      (node (ref "C3") (pin "2") (pinfunction "2_2") (pintype "passive"))
      (node (ref "C5") (pin "2") (pinfunction "2_2") (pintype "passive"))
      (node (ref "TP3") (pin "TP") (pinfunction "TP_TP") (pintype "passive"))
      (node (ref "U1") (pin "12") (pinfunction "MIC1RP/LINE1RP_12") (pintype "input"))
    )
    (net (code "14") (name "/CODEC_IN2L") (class "Default")
      (node (ref "C6") (pin "2") (pinfunction "2_2") (pintype "passive"))
      (node (ref "C8") (pin "2") (pinfunction "2_2") (pintype "passive"))
      (node (ref "TP4") (pin "TP") (pinfunction "TP_TP") (pintype "passive"))
      (node (ref "U1") (pin "14") (pinfunction "MIC2L/LINE2L/MICDET_14") (pintype "input"))
    )
    (net (code "15") (name "/CODEC_IN2R") (class "Default")
      (node (ref "C13") (pin "2") (pinfunction "2_2") (pintype "passive"))
      (node (ref "C14") (pin "2") (pinfunction "2_2") (pintype "passive"))
      (node (ref "TP7") (pin "TP") (pinfunction "TP_TP") (pintype "passive"))
      (node (ref "U1") (pin "16") (pinfunction "MIC2R/LINE2R_16") (pintype "input"))
    )
    (net (code "16") (name "/CODEC_LEFT_LO_N") (class "Default")
      (node (ref "R15") (pin "1") (pinfunction "1_1") (pintype "passive"))
      (node (ref "U1") (pin "28") (pinfunction "LEFT_LOM_28") (pintype "output"))
    )
    (net (code "17") (name "/CODEC_LEFT_LO_P") (class "Default")
      (node (ref "R9") (pin "1") (pinfunction "1_1") (pintype "passive"))
      (node (ref "U1") (pin "27") (pinfunction "LEFT_LOP_27") (pintype "output"))
    )
    (net (code "18") (name "/CODEC_MCLK") (class "Default")
      (node (ref "U1") (pin "1") (pinfunction "MCLK_1") (pintype "input"))
    )
    (net (code "19") (name "/CODEC_RESET_N") (class "Default")
      (node (ref "C19") (pin "2") (pinfunction "2_2") (pintype "passive"))
      (node (ref "R8") (pin "1") (pinfunction "1_1") (pintype "passive"))
      (node (ref "U1") (pin "31") (pinfunction "~{RESET}_31") (pintype "input"))
    )
    (net (code "20") (name "/CODEC_RIGHT_LO_N") (class "Default")
      (node (ref "R16") (pin "1") (pinfunction "1_1") (pintype "passive"))
      (node (ref "U1") (pin "30") (pinfunction "RIGHT_LOM_30") (pintype "output"))
    )
    (net (code "21") (name "/CODEC_RIGHT_LO_P") (class "Default")
      (node (ref "R10") (pin "1") (pinfunction "1_1") (pintype "passive"))
      (node (ref "U1") (pin "29") (pinfunction "RIGHT_LOP_29") (pintype "output"))
    )
    (net (code "22") (name "/CODEC_WCLK") (class "Default")
      (node (ref "U1") (pin "3") (pinfunction "WCLK_3") (pintype "bidirectional"))
    )
    (net (code "23") (name "/EXT_IN1L_N") (class "Default")
      (node (ref "C9") (pin "1") (pinfunction "1_1") (pintype "passive"))
      (node (ref "J7") (pin "2") (pinfunction "2_2") (pintype "passive"))
    )
    (net (code "24") (name "/EXT_IN1L_P") (class "Default")
      (node (ref "C2") (pin "1") (pinfunction "1_1") (pintype "passive"))
      (node (ref "J7") (pin "1") (pinfunction "1_1") (pintype "passive"))
    )
    (net (code "25") (name "/EXT_IN1R_N") (class "Default")
      (node (ref "C10") (pin "1") (pinfunction "1_1") (pintype "passive"))
      (node (ref "J8") (pin "2") (pinfunction "2_2") (pintype "passive"))
    )
    (net (code "26") (name "/EXT_IN1R_P") (class "Default")
      (node (ref "C3") (pin "1") (pinfunction "1_1") (pintype "passive"))
      (node (ref "J8") (pin "1") (pinfunction "1_1") (pintype "passive"))
    )
    (net (code "27") (name "/EXT_IN2L") (class "Default")
      (node (ref "C6") (pin "1") (pinfunction "1_1") (pintype "passive"))
      (node (ref "J11") (pin "1") (pinfunction "1_1") (pintype "passive"))
      (node (ref "R4") (pin "2") (pinfunction "2_2") (pintype "passive"))
    )
    (net (code "28") (name "/EXT_IN2R") (class "Default")
      (node (ref "C13") (pin "1") (pinfunction "1_1") (pintype "passive"))
      (node (ref "J11") (pin "2") (pinfunction "2_2") (pintype "passive"))
      (node (ref "R5") (pin "2") (pinfunction "2_2") (pintype "passive"))
    )
    (net (code "29") (name "/HPLCOM") (class "Default")
      (node (ref "J22") (pin "2") (pinfunction "2_2") (pintype "passive"))
      (node (ref "R13") (pin "2") (pinfunction "2_2") (pintype "passive"))
    )
    (net (code "30") (name "/HPLOUT") (class "Default")
      (node (ref "J22") (pin "3") (pinfunction "3_3") (pintype "passive"))
      (node (ref "R11") (pin "2") (pinfunction "2_2") (pintype "passive"))
    )
    (net (code "31") (name "/HPRCOM") (class "Default")
      (node (ref "J23") (pin "2") (pinfunction "2_2") (pintype "passive"))
      (node (ref "R14") (pin "2") (pinfunction "2_2") (pintype "passive"))
    )
    (net (code "32") (name "/HPROUT") (class "Default")
      (node (ref "J23") (pin "3") (pinfunction "3_3") (pintype "passive"))
      (node (ref "R12") (pin "2") (pinfunction "2_2") (pintype "passive"))
    )
    (net (code "33") (name "/LEFT_LO_N") (class "Default")
      (node (ref "C36") (pin "1") (pinfunction "1_1") (pintype "passive"))
      (node (ref "J20") (pin "2") (pinfunction "2_2") (pintype "passive"))
      (node (ref "R15") (pin "2") (pinfunction "2_2") (pintype "passive"))
      (node (ref "TP16") (pin "TP") (pinfunction "TP_TP") (pintype "passive"))
    )
    (net (code "34") (name "/LEFT_LO_P") (class "Default")
      (node (ref "C26") (pin "1") (pinfunction "1_1") (pintype "passive"))
      (node (ref "J20") (pin "1") (pinfunction "1_1") (pintype "passive"))
      (node (ref "R9") (pin "2") (pinfunction "2_2") (pintype "passive"))
      (node (ref "TP8") (pin "TP") (pinfunction "TP_TP") (pintype "passive"))
    )
    (net (code "35") (name "/MICBIAS") (class "Default")
      (node (ref "C1") (pin "2") (pinfunction "2_2") (pintype "passive"))
      (node (ref "J5") (pin "03") (pinfunction "03_03") (pintype "passive"))
      (node (ref "TP1") (pin "TP") (pinfunction "TP_TP") (pintype "passive"))
      (node (ref "U1") (pin "15") (pinfunction "MICBIAS_15") (pintype "output"))
    )
    (net (code "36") (name "/RIGHT_LO_N") (class "Default")
      (node (ref "C37") (pin "1") (pinfunction "1_1") (pintype "passive"))
      (node (ref "J21") (pin "2") (pinfunction "2_2") (pintype "passive"))
      (node (ref "R16") (pin "2") (pinfunction "2_2") (pintype "passive"))
      (node (ref "TP17") (pin "TP") (pinfunction "TP_TP") (pintype "passive"))
    )
    (net (code "37") (name "/RIGHT_LO_P") (class "Default")
      (node (ref "C27") (pin "1") (pinfunction "1_1") (pintype "passive"))
      (node (ref "J21") (pin "1") (pinfunction "1_1") (pintype "passive"))
      (node (ref "R10") (pin "2") (pinfunction "2_2") (pintype "passive"))
      (node (ref "TP9") (pin "TP") (pinfunction "TP_TP") (pintype "passive"))
    )
    (net (code "38") (name "/SEL_IN2L") (class "Default")
      (node (ref "J6") (pin "2") (pinfunction "tip_2") (pintype "passive"))
      (node (ref "R1") (pin "2") (pinfunction "2_2") (pintype "passive"))
      (node (ref "R4") (pin "1") (pinfunction "1_1") (pintype "passive"))
    )
    (net (code "39") (name "/SEL_IN2R") (class "Default")
      (node (ref "J6") (pin "3") (pinfunction "ring_3") (pintype "passive"))
      (node (ref "R2") (pin "2") (pinfunction "2_2") (pintype "passive"))
      (node (ref "R5") (pin "1") (pinfunction "1_1") (pintype "passive"))
    )
    (net (code "40") (name "1V8") (class "Default")
      (node (ref "J15") (pin "02") (pinfunction "02_02") (pintype "passive"))
    )
    (net (code "41") (name "3V3") (class "Default")
      (node (ref "J12") (pin "02") (pinfunction "02_02") (pintype "passive"))
      (node (ref "J13") (pin "02") (pinfunction "02_02") (pintype "passive"))
      (node (ref "J14") (pin "02") (pinfunction "02_02") (pintype "passive"))
      (node (ref "R3") (pin "2") (pinfunction "2_2") (pintype "passive"))
    )
    (net (code "42") (name "AVDD") (class "Default")
      (node (ref "C15") (pin "2") (pinfunction "2_2") (pintype "passive"))
      (node (ref "C16") (pin "1") (pinfunction "1_1") (pintype "passive"))
      (node (ref "J12") (pin "01") (pinfunction "01_01") (pintype "passive"))
      (node (ref "U1") (pin "25") (pinfunction "AVDD_25") (pintype "power_in"))
    )
    (net (code "43") (name "DRVDD") (class "Default")
      (node (ref "C17") (pin "2") (pinfunction "2_2") (pintype "passive"))
      (node (ref "C18") (pin "1") (pinfunction "1_1") (pintype "passive"))
      (node (ref "J13") (pin "01") (pinfunction "01_01") (pintype "passive"))
      (node (ref "U1") (pin "18") (pinfunction "DRVDD_18") (pintype "power_in"))
      (node (ref "U1") (pin "24") (pinfunction "DRVDD_24") (pintype "power_in"))
    )
    (net (code "44") (name "DVDD") (class "Default")
      (node (ref "C22") (pin "2") (pinfunction "2_2") (pintype "passive"))
      (node (ref "C23") (pin "1") (pinfunction "1_1") (pintype "passive"))
      (node (ref "J15") (pin "01") (pinfunction "01_01") (pintype "passive"))
      (node (ref "U1") (pin "32") (pinfunction "DVDD_32") (pintype "power_in"))
    )
    (net (code "45") (name "GND") (class "Default")
      (node (ref "C1") (pin "1") (pinfunction "1_1") (pintype "passive"))
      (node (ref "C11") (pin "1") (pinfunction "1_1") (pintype "passive"))
      (node (ref "C12") (pin "1") (pinfunction "1_1") (pintype "passive"))
      (node (ref "C14") (pin "1") (pinfunction "1_1") (pintype "passive"))
      (node (ref "C15") (pin "1") (pinfunction "1_1") (pintype "passive"))
      (node (ref "C16") (pin "2") (pinfunction "2_2") (pintype "passive"))
      (node (ref "C17") (pin "1") (pinfunction "1_1") (pintype "passive"))
      (node (ref "C18") (pin "2") (pinfunction "2_2") (pintype "passive"))
      (node (ref "C19") (pin "1") (pinfunction "1_1") (pintype "passive"))
      (node (ref "C20") (pin "1") (pinfunction "1_1") (pintype "passive"))
      (node (ref "C21") (pin "2") (pinfunction "2_2") (pintype "passive"))
      (node (ref "C22") (pin "1") (pinfunction "1_1") (pintype "passive"))
      (node (ref "C23") (pin "2") (pinfunction "2_2") (pintype "passive"))
      (node (ref "C26") (pin "2") (pinfunction "2_2") (pintype "passive"))
      (node (ref "C27") (pin "2") (pinfunction "2_2") (pintype "passive"))
      (node (ref "C28") (pin "1") (pinfunction "1_1") (pintype "passive"))
      (node (ref "C29") (pin "1") (pinfunction "1_1") (pintype "passive"))
      (node (ref "C34") (pin "1") (pinfunction "1_1") (pintype "passive"))
      (node (ref "C35") (pin "1") (pinfunction "1_1") (pintype "passive"))
      (node (ref "C36") (pin "2") (pinfunction "2_2") (pintype "passive"))
      (node (ref "C37") (pin "2") (pinfunction "2_2") (pintype "passive"))
      (node (ref "C4") (pin "1") (pinfunction "1_1") (pintype "passive"))
      (node (ref "C5") (pin "1") (pinfunction "1_1") (pintype "passive"))
      (node (ref "C7") (pin "1") (pinfunction "1_1") (pintype "passive"))
      (node (ref "C8") (pin "1") (pinfunction "1_1") (pintype "passive"))
      (node (ref "J11") (pin "3") (pinfunction "3_3") (pintype "passive"))
      (node (ref "J22") (pin "1") (pinfunction "1_1") (pintype "passive"))
      (node (ref "J23") (pin "1") (pinfunction "1_1") (pintype "passive"))
      (node (ref "J6") (pin "1") (pinfunction "sleeve_1") (pintype "passive"))
      (node (ref "J7") (pin "3") (pinfunction "3_3") (pintype "passive"))
      (node (ref "J8") (pin "3") (pinfunction "3_3") (pintype "passive"))
      (node (ref "MIC1") (pin "N") (pinfunction "N_N") (pintype "passive"))
      (node (ref "S1") (pin "9") (pinfunction "9_9") (pintype "passive"))
      (node (ref "U1") (pin "17") (pinfunction "AVSS_17") (pintype "power_in"))
      (node (ref "U1") (pin "21") (pinfunction "DRVSS_21") (pintype "power_in"))
      (node (ref "U1") (pin "26") (pinfunction "AVSS_26") (pintype "power_in"))
      (node (ref "U1") (pin "33") (pinfunction "EP_33") (pintype "power_in"))
      (node (ref "U1") (pin "6") (pinfunction "DVSS_6") (pintype "power_in"))
    )
    (net (code "46") (name "IOVDD") (class "Default")
      (node (ref "C20") (pin "2") (pinfunction "2_2") (pintype "passive"))
      (node (ref "C21") (pin "1") (pinfunction "1_1") (pintype "passive"))
      (node (ref "J14") (pin "01") (pinfunction "01_01") (pintype "passive"))
      (node (ref "R6") (pin "2") (pinfunction "2_2") (pintype "passive"))
      (node (ref "R7") (pin "2") (pinfunction "2_2") (pintype "passive"))
      (node (ref "R8") (pin "2") (pinfunction "2_2") (pintype "passive"))
      (node (ref "U1") (pin "7") (pinfunction "IOVDD_7") (pintype "power_in"))
    )
    (net (code "47") (name "Net-(C7-Pad2)") (class "Default")
      (node (ref "C7") (pin "2") (pinfunction "2_2") (pintype "passive"))
      (node (ref "J5") (pin "01") (pinfunction "01_01") (pintype "passive"))
      (node (ref "R3") (pin "1") (pinfunction "1_1") (pintype "passive"))
    )
    (net (code "48") (name "Net-(C24-PadN)") (class "Default")
      (node (ref "C24") (pin "N") (pinfunction "N_N") (pintype "passive"))
      (node (ref "C28") (pin "2") (pinfunction "2_2") (pintype "passive"))
      (node (ref "J18") (pin "02") (pinfunction "02_02") (pintype "passive"))
      (node (ref "R11") (pin "1") (pinfunction "1_1") (pintype "passive"))
      (node (ref "TP10") (pin "TP") (pinfunction "TP_TP") (pintype "passive"))
    )
    (net (code "49") (name "Net-(C25-PadN)") (class "Default")
      (node (ref "C25") (pin "N") (pinfunction "N_N") (pintype "passive"))
      (node (ref "C29") (pin "2") (pinfunction "2_2") (pintype "passive"))
      (node (ref "J19") (pin "02") (pinfunction "02_02") (pintype "passive"))
      (node (ref "R12") (pin "1") (pinfunction "1_1") (pintype "passive"))
      (node (ref "TP11") (pin "TP") (pinfunction "TP_TP") (pintype "passive"))
    )
    (net (code "50") (name "Net-(C30-PadN)") (class "Default")
      (node (ref "C30") (pin "N") (pinfunction "N_N") (pintype "passive"))
      (node (ref "S1") (pin "3") (pinfunction "3_3") (pintype "passive"))
    )
    (net (code "51") (name "Net-(C31-PadN)") (class "Default")
      (node (ref "C31") (pin "N") (pinfunction "N_N") (pintype "passive"))
      (node (ref "S1") (pin "6") (pinfunction "6_6") (pintype "passive"))
    )
    (net (code "52") (name "Net-(C32-PadN)") (class "Default")
      (node (ref "C32") (pin "N") (pinfunction "N_N") (pintype "passive"))
      (node (ref "C34") (pin "2") (pinfunction "2_2") (pintype "passive"))
      (node (ref "J24") (pin "02") (pinfunction "02_02") (pintype "passive"))
      (node (ref "R13") (pin "1") (pinfunction "1_1") (pintype "passive"))
      (node (ref "TP14") (pin "TP") (pinfunction "TP_TP") (pintype "passive"))
    )
    (net (code "53") (name "Net-(C33-PadN)") (class "Default")
      (node (ref "C33") (pin "N") (pinfunction "N_N") (pintype "passive"))
      (node (ref "C35") (pin "2") (pinfunction "2_2") (pintype "passive"))
      (node (ref "J25") (pin "02") (pinfunction "02_02") (pintype "passive"))
      (node (ref "R14") (pin "1") (pinfunction "1_1") (pintype "passive"))
      (node (ref "TP15") (pin "TP") (pinfunction "TP_TP") (pintype "passive"))
    )
    (net (code "54") (name "Net-(J5-Pad02)") (class "Default")
      (node (ref "J5") (pin "02") (pinfunction "02_02") (pintype "passive"))
      (node (ref "R1") (pin "1") (pinfunction "1_1") (pintype "passive"))
      (node (ref "R2") (pin "1") (pinfunction "1_1") (pintype "passive"))
    )
    (net (code "55") (name "Net-(J6-ring_switch)") (class "Default")
      (node (ref "J6") (pin "11") (pinfunction "ring_switch_11") (pintype "passive"))
      (node (ref "J9") (pin "02") (pinfunction "02_02") (pintype "passive"))
    )
    (net (code "56") (name "Net-(J6-tip_switch)") (class "Default")
      (node (ref "J10") (pin "02") (pinfunction "02_02") (pintype "passive"))
      (node (ref "J6") (pin "10") (pinfunction "tip_switch_10") (pintype "passive"))
    )
    (net (code "57") (name "Net-(J10-Pad01)") (class "Default")
      (node (ref "J10") (pin "01") (pinfunction "01_01") (pintype "passive"))
      (node (ref "J9") (pin "01") (pinfunction "01_01") (pintype "passive"))
      (node (ref "MIC1") (pin "P") (pinfunction "P_P") (pintype "passive"))
    )
    (net (code "58") (name "Net-(J17-ring)") (class "Default")
      (node (ref "J17") (pin "3") (pinfunction "ring_3") (pintype "passive"))
      (node (ref "S1") (pin "5") (pinfunction "5_5") (pintype "passive"))
    )
    (net (code "59") (name "Net-(J17-sleeve)") (class "Default")
      (node (ref "J17") (pin "1") (pinfunction "sleeve_1") (pintype "passive"))
      (node (ref "S1") (pin "8") (pinfunction "8_8") (pintype "passive"))
    )
    (net (code "60") (name "Net-(J17-tip)") (class "Default")
      (node (ref "J17") (pin "2") (pinfunction "tip_2") (pintype "passive"))
      (node (ref "S1") (pin "2") (pinfunction "2_2") (pintype "passive"))
    )
    (net (code "61") (name "unconnected-(J17-ring_switch-Pad11)") (class "Default")
      (node (ref "J17") (pin "11") (pinfunction "ring_switch_11") (pintype "passive+no_connect"))
    )
    (net (code "62") (name "unconnected-(J17-tip_switch-Pad10)") (class "Default")
      (node (ref "J17") (pin "10") (pinfunction "tip_switch_10") (pintype "passive+no_connect"))
    )
    (net (code "63") (name "unconnected-(S1-Pad10)") (class "Default")
      (node (ref "S1") (pin "10") (pinfunction "10_10") (pintype "passive+no_connect"))
    )
    (net (code "64") (name "unconnected-(S1-Pad11)") (class "Default")
      (node (ref "S1") (pin "11") (pinfunction "11_11") (pintype "passive+no_connect"))
    )
    (net (code "65") (name "unconnected-(S1-Pad12)") (class "Default")
      (node (ref "S1") (pin "12") (pinfunction "12_12") (pintype "passive+no_connect"))
    )
  )
)
